# Channel.net
KiCad netlist of a schematic drawn in Altium Designer
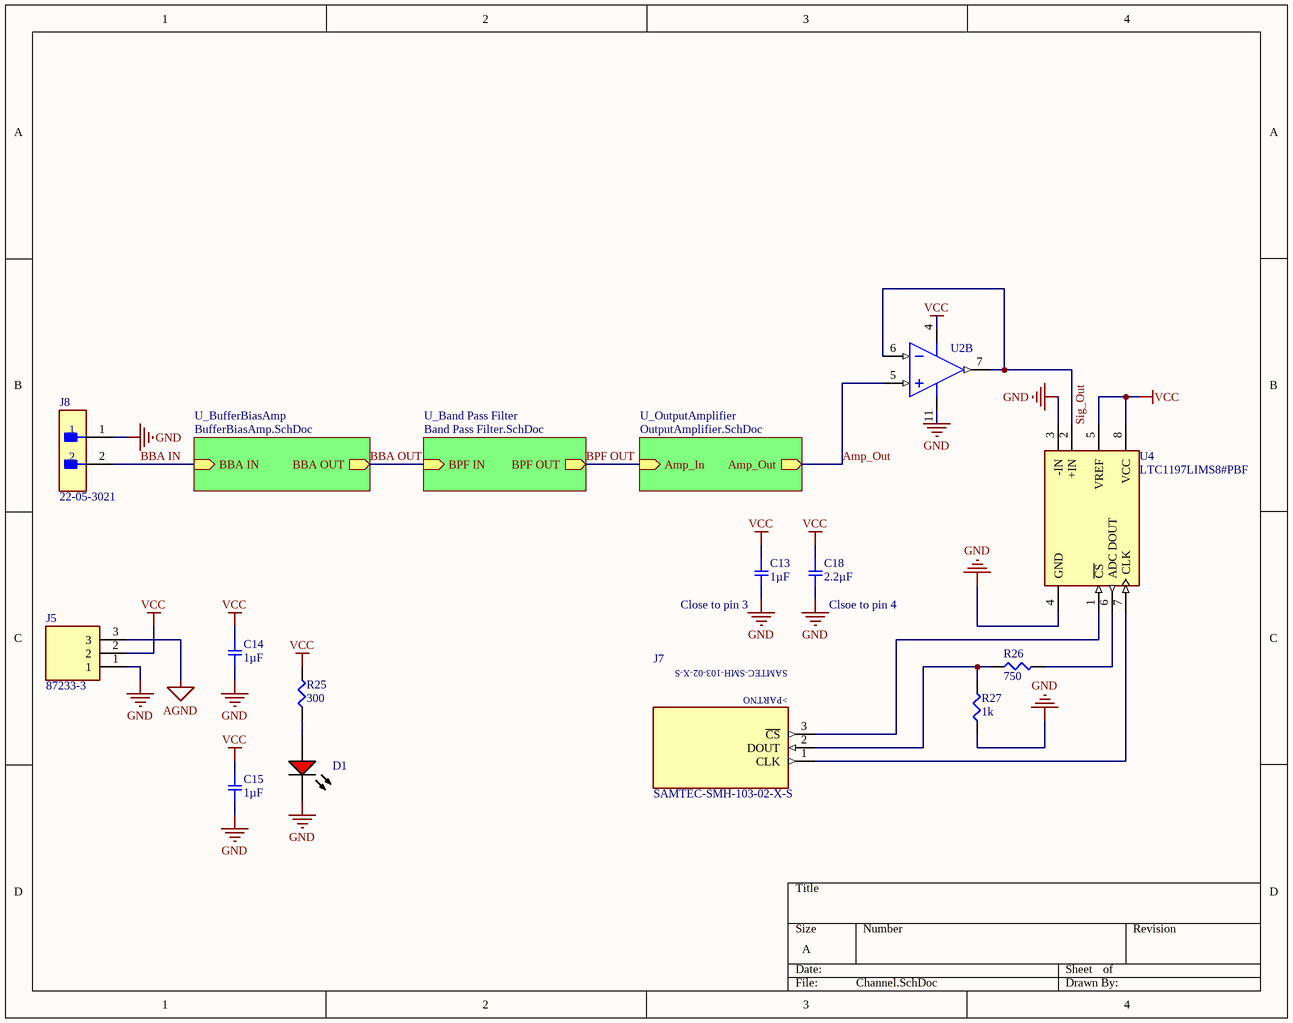
[diagram p0: Channel.SchDoc]

(export (version "E")
  (design (tool "Eeschema 10.0.6"))
  (components
    (comp (ref "C13")
      (value "1µF")
      (footprint "SMD-0603C")
      (description "CAP CER 1UF 6.3V X6S 0603")
      (fields
        (field (name "DIGI-KEY PART NUMBER") "490-8271-1-ND")
        (field (name "PART NUMBER") "GRM185C80J105KE26D")
      )
      (libsource (lib "capacitor_murata_0603") (part "GRM185C80J105KE26D"))
    )
    (comp (ref "C14")
      (value "1µF")
      (footprint "SMD-0603C")
      (description "CAP CER 1UF 16V X7R 0603")
      (fields
        (field (name "MANUFACTURER") "Samsung Electro-Mechanics")
        (field (name "MANUFACTURER PART NUMBER") "CL10A105KA8NNNC")
      )
      (libsource (lib "capacitor_murata_0603") (part "GCM188R71C105KA64D"))
    )
    (comp (ref "C15")
      (value "1µF")
      (footprint "SMD-0603C")
      (description "CAP CER 1UF 16V X7R 0603")
      (fields
        (field (name "MANUFACTURER") "Samsung Electro-Mechanics")
        (field (name "MANUFACTURER PART NUMBER") "CL10A105KA8NNNC")
      )
      (libsource (lib "capacitor_murata_0603") (part "GCM188R71C105KA64D"))
    )
    (comp (ref "C18")
      (value "2.2µF")
      (footprint "SMD-0603C")
      (description "CAP CER 2.2UF 6.3V X7R 0603")
      (fields
        (field (name "DIGI-KEY PART NUMBER") "490-5316-1-ND")
        (field (name "PART NUMBER") "GCM188R70J225KE22D")
      )
      (libsource (lib "capacitor_murata_0603") (part "GCM188R70J225KE22D"))
    )
    (comp (ref "D1")
      (value "TLMS1100-GS08")
      (footprint "VISH-TLMX1100_V")
      (description "LED, RED, 2.1 V, -40 to 100 degC, 2-Pin SMD (0603), RoHS, Tape and Reel")
      (fields
        (field (name "MANUFACTURER") "Wurth Elektronics")
        (field (name "MANUFACTURER PART NUMBER") "150080SS75000")
      )
      (libsource (lib "Altium Content Vault") (part "LED-RED-AK-2"))
    )
    (comp (ref "J5")
      (value "87233-3")
      (footprint "TE_87233-3")
      (fields (field (name "MF") "{'manufacturer': u'TE Connectivity'}"))
      (libsource (lib "87233-3") (part "87233-3"))
    )
    (comp (ref "J7")
      (value "SAMTEC-SMH-103-02-X-S")
      (footprint "SMH-103-02-G-S:SAMTEC-SMH-103-02-X-S")
      (fields (field (name "MF") "{'manufacturer': u'Samtec'}"))
      (libsource (lib "*") (part "SAMTEC-SMH-103-02-X-S"))
    )
    (comp (ref "J8")
      (value "22-05-3021")
      (footprint "FP-22-05-3021-MFG")
      (description "CONN HEADER R/A 2POS 2.54MM")
      (libsource (lib "Altium Content Vault") (part "3bc925449376181038e59eaffc5286c"))
    )
    (comp (ref "R25")
      (value "300")
      (footprint "SMD-0603-RES")
      (description "RES SMD 300 OHM 1% 1/10W 0603")
      (fields
        (field (name "MANUFACTURER") "Panasonic Electronic Components")
        (field (name "MANUFACTURER PART NUMBER") "ERJ-3EKF3000V")
      )
      (libsource (lib "Panasonic_resistor_0603") (part "ERJ-3EKF3000V"))
    )
    (comp (ref "R26")
      (value "750")
      (footprint "SMD-0603-RES")
      (description "RES SMD 750 OHM 1% 1/10W 0603")
      (fields (field (name "PART NUMBER") "ERJ-3EKF7500V") (field (name "DIGI-KEY PART NUMBER") "P750HCT-ND"))
      (libsource (lib "Panasonic_resistor_0603") (part "ERJ-3EKF7500V"))
    )
    (comp (ref "R27")
      (value "1k")
      (footprint "SMD-0603-RES")
      (description "RES SMD 1K OHM 1% 1/10W 0603")
      (fields
        (field (name "PART NUMBER") "ERJ-3EKF1001V")
        (field (name "DIGI-KEY PART NUMBER") "P1.00KHCT-ND")
      )
      (libsource (lib "Panasonic_resistor_0603") (part "ERJ-3EKF1001V"))
    )
    (comp (ref "U2")
      (value "OPA1604AIPWR")
      (footprint "PW0014A_N")
      (fields (field (name "MANUFACTURER") "Texas Instruments"))
      (libsource (lib "Altium Content Vault") (part "TI-OPA16X4_4XXX-14"))
    )
    (comp (ref "U4")
      (value "LTC1197LIMS8#PBF")
      (footprint "FP-MS8-8-05-08-1660-IPC_A")
      (description "IC ADC 10BIT SAR 8MSOP")
      (libsource (lib "Altium Content Vault") (part "b4ff916109b4f52b6d17af6699a3653"))
    )
  )
  (nets
    (net (code "1") (name "/Amp_Out") (class "Default")
      (node (ref "U2") (pin "5") (pinfunction "IN_B+_5") (pintype "input"))
    )
    (net (code "2") (name "/BBA IN") (class "Default")
      (node (ref "J8") (pin "2") (pinfunction "2_2") (pintype "passive"))
    )
    (net (code "5") (name "/Sig_Out") (class "Default")
      (node (ref "U2") (pin "6") (pinfunction "IN_B-_6") (pintype "input"))
      (node (ref "U2") (pin "7") (pinfunction "OUT_B_7") (pintype "output"))
      (node (ref "U4") (pin "2") (pinfunction "+IN_2") (pintype "passive"))
    )
    (net (code "6") (name "AGND") (class "Default")
      (node (ref "J5") (pin "3") (pinfunction "3_3") (pintype "power_in"))
    )
    (net (code "7") (name "GND") (class "Default")
      (node (ref "C13") (pin "2") (pinfunction "2_2") (pintype "passive"))
      (node (ref "C14") (pin "1") (pinfunction "1_1") (pintype "passive"))
      (node (ref "C15") (pin "1") (pinfunction "1_1") (pintype "passive"))
      (node (ref "C18") (pin "2") (pinfunction "2_2") (pintype "passive"))
      (node (ref "D1") (pin "2") (pinfunction "K_2") (pintype "passive"))
      (node (ref "J5") (pin "1") (pinfunction "1_1") (pintype "power_in"))
      (node (ref "J8") (pin "1") (pinfunction "1_1") (pintype "passive"))
      (node (ref "R27") (pin "1") (pinfunction "1_1") (pintype "passive"))
      (node (ref "U2") (pin "11") (pinfunction "V-_11") (pintype "power_in"))
      (node (ref "U4") (pin "3") (pinfunction "-IN_3") (pintype "passive"))
      (node (ref "U4") (pin "4") (pinfunction "GND_4") (pintype "power_in"))
    )
    (net (code "8") (name "Net-(D1-A)") (class "Default")
      (node (ref "D1") (pin "1") (pinfunction "A_1") (pintype "passive"))
      (node (ref "R25") (pin "1") (pinfunction "1_1") (pintype "passive"))
    )
    (net (code "9") (name "Net-(J7-CLK)") (class "Default")
      (node (ref "J7") (pin "1") (pinfunction "CLK_1") (pintype "output"))
      (node (ref "U4") (pin "7") (pinfunction "CLK_7") (pintype "input"))
    )
    (net (code "10") (name "Net-(J7-DOUT)") (class "Default")
      (node (ref "J7") (pin "2") (pinfunction "DOUT_2") (pintype "input"))
      (node (ref "R26") (pin "1") (pinfunction "1_1") (pintype "passive"))
      (node (ref "R27") (pin "2") (pinfunction "2_2") (pintype "passive"))
    )
    (net (code "11") (name "Net-(J7-~{CS})") (class "Default")
      (node (ref "J7") (pin "3") (pinfunction "~{CS}_3") (pintype "output"))
      (node (ref "U4") (pin "1") (pinfunction "~{CS}_1") (pintype "input"))
    )
    (net (code "12") (name "Net-(U4-ADC_DOUT)") (class "Default")
      (node (ref "R26") (pin "2") (pinfunction "2_2") (pintype "passive"))
      (node (ref "U4") (pin "6") (pinfunction "ADC_DOUT_6") (pintype "output"))
    )
    (net (code "13") (name "VCC") (class "Default")
      (node (ref "C13") (pin "1") (pinfunction "1_1") (pintype "passive"))
      (node (ref "C14") (pin "2") (pinfunction "2_2") (pintype "passive"))
      (node (ref "C15") (pin "2") (pinfunction "2_2") (pintype "passive"))
      (node (ref "C18") (pin "1") (pinfunction "1_1") (pintype "passive"))
      (node (ref "J5") (pin "2") (pinfunction "2_2") (pintype "power_in"))
      (node (ref "R25") (pin "2") (pinfunction "2_2") (pintype "passive"))
      (node (ref "U2") (pin "4") (pinfunction "V+_4") (pintype "power_in"))
      (node (ref "U4") (pin "5") (pinfunction "VREF_5") (pintype "passive"))
      (node (ref "U4") (pin "8") (pinfunction "VCC_8") (pintype "power_in"))
    )
  )
)
